# OLEDCard_ChinaUS_Maker.net
KiCad netlist of a schematic drawn in Altium Designer
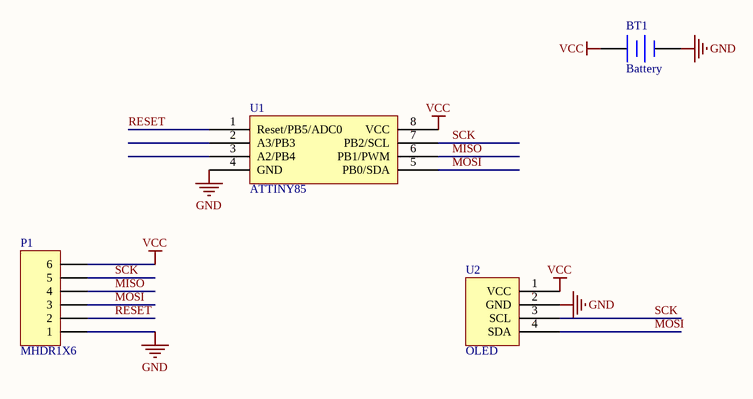
[diagram p0: OLEDCard_ChinaUS_Maker.SchDoc]

(export (version "E")
  (design (tool "Eeschema 10.0.6"))
  (components
    (comp (ref "BT1")
      (value "Battery")
      (footprint "BATTCON_20MM_4LEGS")
      (description "Multicell Battery")
      (fields (field (name "PUBLISHER") "Altium Limited"))
      (libsource (lib "Miscellaneous Devices") (part "Battery"))
    )
    (comp (ref "P1")
      (value "MHDR1X6")
      (footprint "HDR1X6")
      (description "Header, 6-Pin")
      (fields (field (name "PUBLISHER") "Altium Limited"))
      (libsource (lib "Miscellaneous Connectors") (part "MHDR1X6"))
    )
    (comp (ref "U1") (value "ATTINY85") (footprint "DIP-P8") (libsource (lib "OLED") (part "ATTINY85")))
    (comp (ref "U2") (value "OLED") (footprint "OLED") (libsource (lib "OLED") (part "OLED")))
  )
  (nets
    (net (code "1") (name "/MISO") (class "Default")
      (node (ref "P1") (pin "4") (pinfunction "4_4") (pintype "passive"))
      (node (ref "U1") (pin "6") (pinfunction "PB1/PWM_6") (pintype "passive"))
    )
    (net (code "2") (name "/MOSI") (class "Default")
      (node (ref "P1") (pin "3") (pinfunction "3_3") (pintype "passive"))
      (node (ref "U1") (pin "5") (pinfunction "PB0/SDA_5") (pintype "passive"))
      (node (ref "U2") (pin "4") (pinfunction "SDA_4") (pintype "passive"))
    )
    (net (code "3") (name "/RESET") (class "Default")
      (node (ref "P1") (pin "2") (pinfunction "2_2") (pintype "passive"))
      (node (ref "U1") (pin "1") (pinfunction "Reset/PB5/ADC0_1") (pintype "passive"))
    )
    (net (code "4") (name "/SCK") (class "Default")
      (node (ref "P1") (pin "5") (pinfunction "5_5") (pintype "passive"))
      (node (ref "U1") (pin "7") (pinfunction "PB2/SCL_7") (pintype "passive"))
      (node (ref "U2") (pin "3") (pinfunction "SCL_3") (pintype "passive"))
    )
    (net (code "5") (name "GND") (class "Default")
      (node (ref "BT1") (pin "2") (pinfunction "-_2") (pintype "passive"))
      (node (ref "P1") (pin "1") (pinfunction "1_1") (pintype "passive"))
      (node (ref "U1") (pin "4") (pinfunction "GND_4") (pintype "passive"))
      (node (ref "U2") (pin "2") (pinfunction "GND_2") (pintype "passive"))
    )
    (net (code "6") (name "VCC") (class "Default")
      (node (ref "BT1") (pin "1") (pinfunction "+_1") (pintype "passive"))
      (node (ref "P1") (pin "6") (pinfunction "6_6") (pintype "passive"))
      (node (ref "U1") (pin "8") (pinfunction "VCC_8") (pintype "passive"))
      (node (ref "U2") (pin "1") (pinfunction "VCC_1") (pintype "passive"))
    )
    (net (code "7") (name "unconnected-(U1-A2{slash}PB4-Pad3)") (class "Default")
      (node (ref "U1") (pin "3") (pinfunction "A2/PB4_3") (pintype "passive"))
    )
    (net (code "8") (name "unconnected-(U1-A3{slash}PB3-Pad2)") (class "Default")
      (node (ref "U1") (pin "2") (pinfunction "A3/PB3_2") (pintype "passive"))
    )
  )
)
